# PiHatTeensy32_40.net
KiCad netlist of a schematic drawn in EAGLE
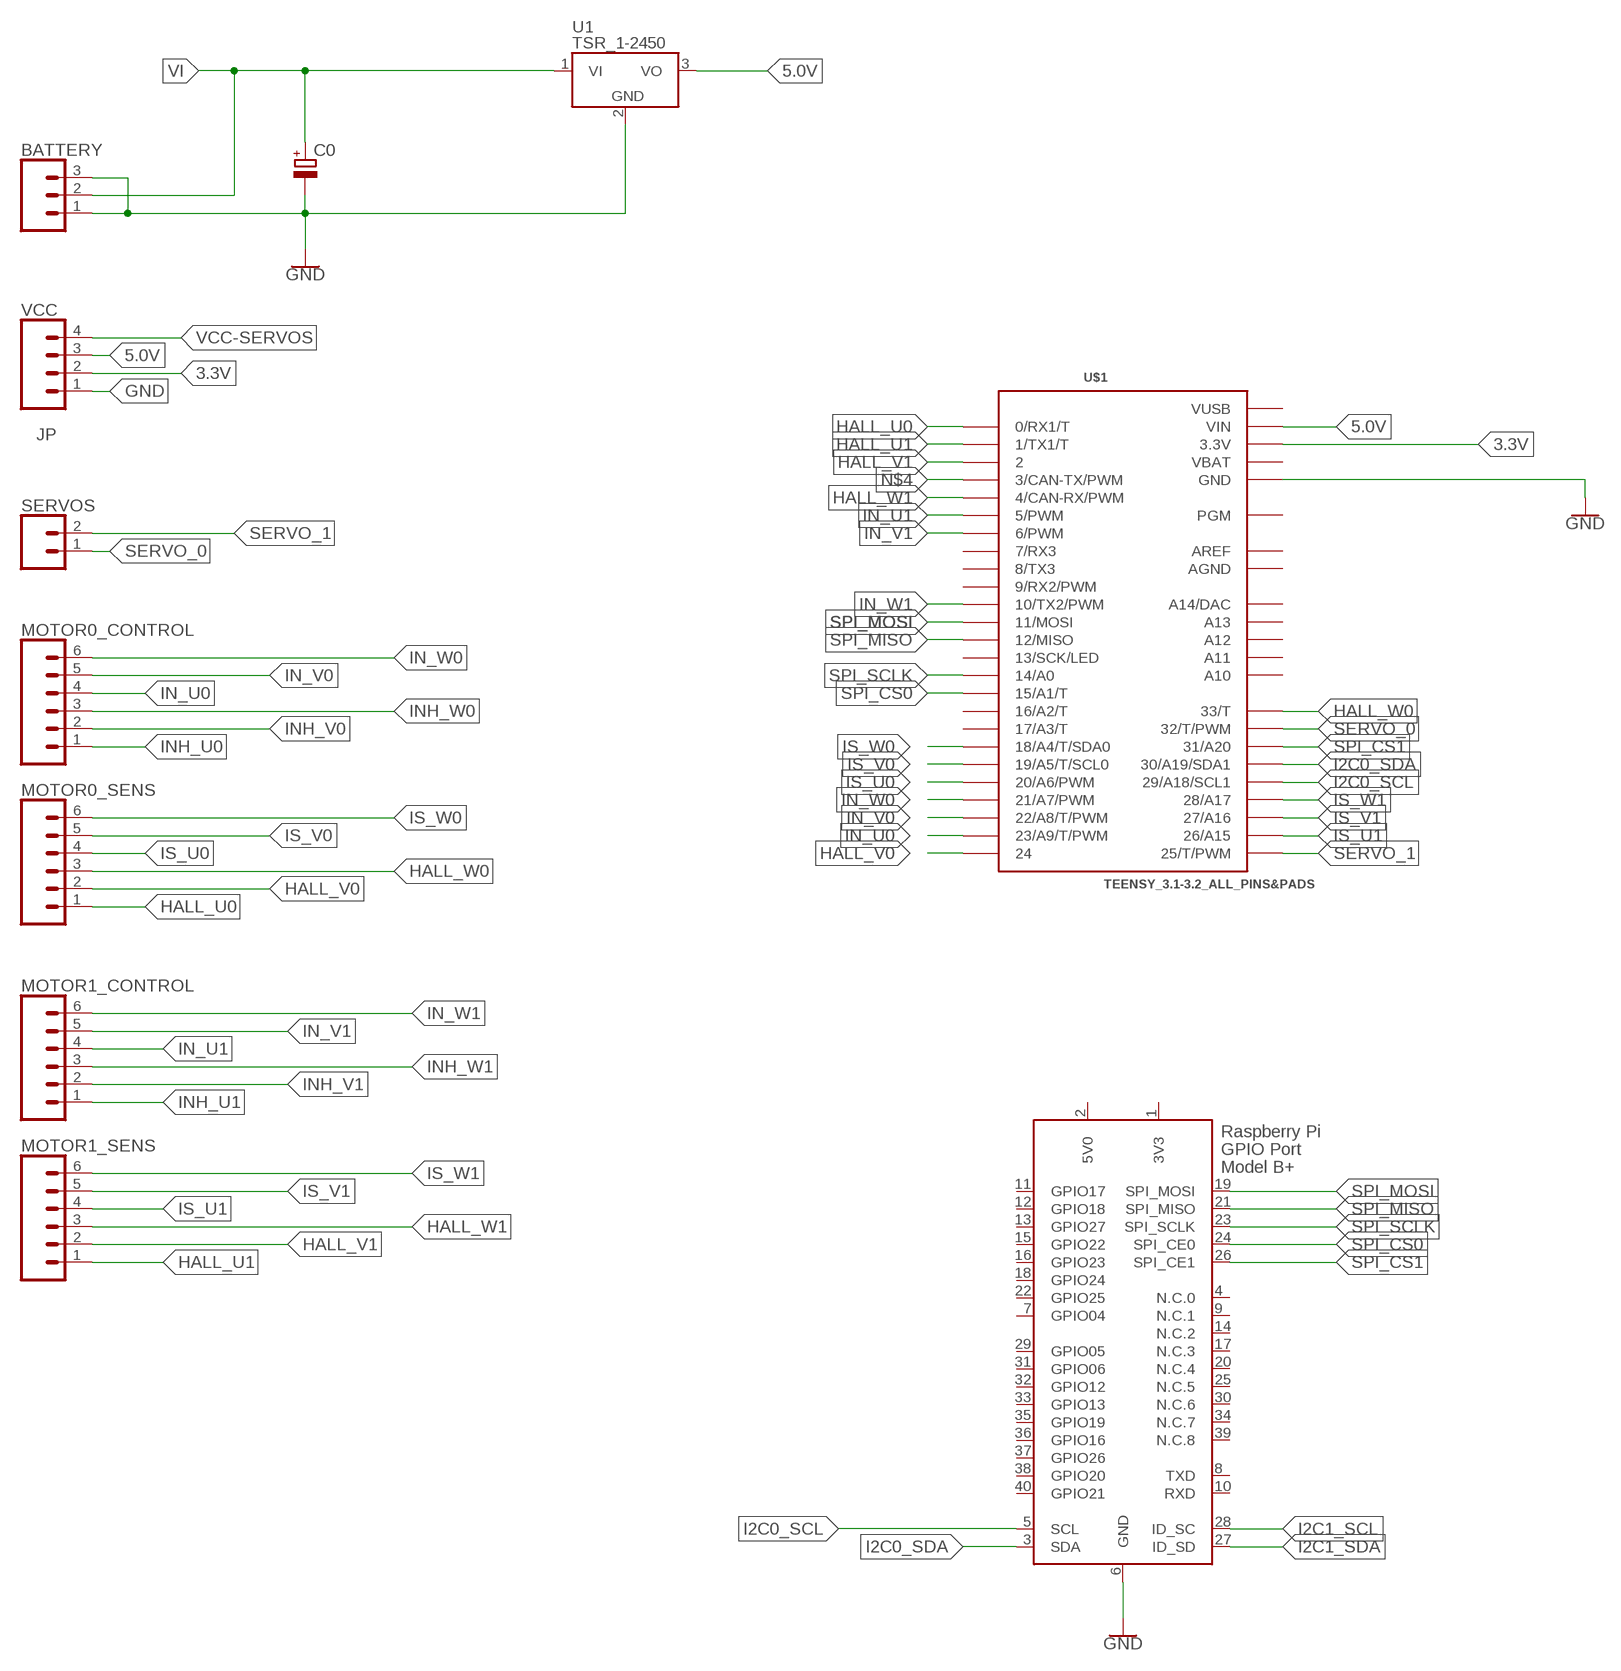
[diagram p0: schematic, sheet 1]

(export (version "E")
  (design (tool "Eeschema 10.0.6"))
  (components
    (comp (ref "BATTERY")
      (value "CONN_031X03_NO_SILK")
      (footprint "eagle-import:1X03_NO_SILK")
      (libsource (lib "eagle-import") (part "CONN_031X03_NO_SILK"))
    )
    (comp (ref "C0")
      (value "CPOL-EUE2,5-6E")
      (footprint "eagle-import:E2,5-6E")
      (libsource (lib "eagle-import") (part "CPOL-EUE2,5-6E"))
    )
    (comp (ref "MOTOR0_CONTROL")
      (value "CONN_06NO_SILK_NO_POP")
      (footprint "eagle-import:1X06_NO_SILK")
      (libsource (lib "eagle-import") (part "CONN_06NO_SILK_NO_POP"))
    )
    (comp (ref "MOTOR0_SENS")
      (value "CONN_06NO_SILK_NO_POP")
      (footprint "eagle-import:1X06_NO_SILK")
      (libsource (lib "eagle-import") (part "CONN_06NO_SILK_NO_POP"))
    )
    (comp (ref "MOTOR1_CONTROL")
      (value "CONN_06NO_SILK_NO_POP")
      (footprint "eagle-import:1X06_NO_SILK")
      (libsource (lib "eagle-import") (part "CONN_06NO_SILK_NO_POP"))
    )
    (comp (ref "MOTOR1_SENS")
      (value "CONN_06NO_SILK_NO_POP")
      (footprint "eagle-import:1X06_NO_SILK")
      (libsource (lib "eagle-import") (part "CONN_06NO_SILK_NO_POP"))
    )
    (comp (ref "SERVOS")
      (value "CONN_021X02_NO_SILK")
      (footprint "eagle-import:1X02_NO_SILK")
      (libsource (lib "eagle-import") (part "CONN_021X02_NO_SILK"))
    )
    (comp (ref "U$1")
      (value "TEENSY_3.1-3.2_ALL_PINS&PADS")
      (footprint "eagle-import:TEENSY_3.0-3.2_ALL_PINS_&_PADS")
      (libsource (lib "eagle-import") (part "TEENSY_3.1-3.2_ALL_PINS&PADS"))
    )
    (comp (ref "U1")
      (value "TSR_1-2450")
      (footprint "eagle-import:TSR-1")
      (libsource (lib "eagle-import") (part "TSR_1-2450"))
    )
    (comp (ref "VCC")
      (value "JP")
      (footprint "eagle-import:1X04_NO_SILK")
      (libsource (lib "eagle-import") (part "CONN_041X04_NO_SILK"))
    )
    (comp (ref "X1")
      (value "RASPI_BOARD_B+_H")
      (footprint "eagle-import:RASPI_BOARD_B+HAT")
      (libsource (lib "eagle-import") (part "RASPI_BOARD_B+_H"))
    )
  )
  (nets
    (net (code "1") (name "/3V3") (class "Default")
      (node (ref "X1") (pin "1") (pinfunction "3V3_1") (pintype "power_in"))
    )
    (net (code "2") (name "/5V0") (class "Default")
      (node (ref "X1") (pin "2") (pinfunction "5V0_2") (pintype "power_in"))
    )
    (net (code "3") (name "/AGND") (class "Default")
      (node (ref "U$1") (pin "AGND") (pinfunction "AGND_AGND") (pintype "power_in"))
    )
    (net (code "4") (name "/AREF") (class "Default")
      (node (ref "U$1") (pin "AREF") (pinfunction "AREF_AREF") (pintype "power_in"))
    )
    (net (code "5") (name "/VBAT") (class "Default")
      (node (ref "U$1") (pin "VBAT") (pinfunction "VBAT_VBAT") (pintype "power_in"))
    )
    (net (code "6") (name "/VUSB") (class "Default")
      (node (ref "U$1") (pin "VUSB") (pinfunction "VUSB_VUSB") (pintype "power_in"))
    )
    (net (code "7") (name "3.3V") (class "Default")
      (node (ref "U$1") (pin "3.3V") (pinfunction "3.3V_3.3V") (pintype "power_in"))
      (node (ref "U$1") (pin "3.3V1") (pinfunction "3.3V_3.3V1") (pintype "power_in"))
      (node (ref "U$1") (pin "3.3V2") (pinfunction "3.3V_3.3V2") (pintype "power_in"))
      (node (ref "VCC") (pin "2") (pinfunction "2_2") (pintype "passive"))
    )
    (net (code "8") (name "5.0V") (class "Default")
      (node (ref "U$1") (pin "VIN") (pinfunction "VIN_VIN") (pintype "power_in"))
      (node (ref "U1") (pin "3") (pinfunction "VO_3") (pintype "power_in"))
      (node (ref "VCC") (pin "3") (pinfunction "3_3") (pintype "passive"))
    )
    (net (code "9") (name "GND") (class "Default")
      (node (ref "BATTERY") (pin "1") (pinfunction "1_1") (pintype "passive"))
      (node (ref "BATTERY") (pin "3") (pinfunction "3_3") (pintype "passive"))
      (node (ref "C0") (pin "-") (pinfunction "-_-") (pintype "passive"))
      (node (ref "U$1") (pin "GND") (pinfunction "GND_GND") (pintype "power_in"))
      (node (ref "U$1") (pin "GND1") (pinfunction "GND_GND1") (pintype "power_in"))
      (node (ref "U$1") (pin "GND2") (pinfunction "GND_GND2") (pintype "power_in"))
      (node (ref "U1") (pin "2") (pinfunction "GND_2") (pintype "power_in"))
      (node (ref "VCC") (pin "1") (pinfunction "1_1") (pintype "passive"))
      (node (ref "X1") (pin "6") (pinfunction "GND_6") (pintype "power_in"))
    )
    (net (code "10") (name "HALL_U0") (class "Default")
      (node (ref "MOTOR0_SENS") (pin "1") (pinfunction "1_1") (pintype "passive"))
      (node (ref "U$1") (pin "0") (pinfunction "0/RX1/T_0") (pintype "bidirectional"))
    )
    (net (code "11") (name "HALL_U1") (class "Default")
      (node (ref "MOTOR1_SENS") (pin "1") (pinfunction "1_1") (pintype "passive"))
      (node (ref "U$1") (pin "1") (pinfunction "1/TX1/T_1") (pintype "bidirectional"))
    )
    (net (code "12") (name "HALL_V0") (class "Default")
      (node (ref "MOTOR0_SENS") (pin "2") (pinfunction "2_2") (pintype "passive"))
      (node (ref "U$1") (pin "24") (pinfunction "24_24") (pintype "bidirectional"))
    )
    (net (code "13") (name "HALL_V1") (class "Default")
      (node (ref "MOTOR1_SENS") (pin "2") (pinfunction "2_2") (pintype "passive"))
      (node (ref "U$1") (pin "2") (pinfunction "2_2") (pintype "bidirectional"))
    )
    (net (code "14") (name "HALL_W0") (class "Default")
      (node (ref "MOTOR0_SENS") (pin "3") (pinfunction "3_3") (pintype "passive"))
      (node (ref "U$1") (pin "33") (pinfunction "33/T_33") (pintype "bidirectional"))
    )
    (net (code "15") (name "HALL_W1") (class "Default")
      (node (ref "MOTOR1_SENS") (pin "3") (pinfunction "3_3") (pintype "passive"))
      (node (ref "U$1") (pin "4") (pinfunction "4/CAN-RX/PWM_4") (pintype "bidirectional"))
    )
    (net (code "16") (name "I2C0_SCL") (class "Default")
      (node (ref "U$1") (pin "29") (pinfunction "29/A18/SCL1_29") (pintype "bidirectional"))
      (node (ref "X1") (pin "5") (pinfunction "SCL_5") (pintype "bidirectional"))
    )
    (net (code "17") (name "I2C0_SDA") (class "Default")
      (node (ref "U$1") (pin "30") (pinfunction "30/A19/SDA1_30") (pintype "bidirectional"))
      (node (ref "X1") (pin "3") (pinfunction "SDA_3") (pintype "bidirectional"))
    )
    (net (code "20") (name "I2C1_SCL") (class "Default")
      (node (ref "X1") (pin "28") (pinfunction "ID_SC_28") (pintype "no_connect"))
    )
    (net (code "21") (name "I2C1_SDA") (class "Default")
      (node (ref "X1") (pin "27") (pinfunction "ID_SD_27") (pintype "no_connect"))
    )
    (net (code "22") (name "INH_U0") (class "Default")
      (node (ref "MOTOR0_CONTROL") (pin "1") (pinfunction "1_1") (pintype "passive"))
    )
    (net (code "23") (name "INH_U1") (class "Default")
      (node (ref "MOTOR1_CONTROL") (pin "1") (pinfunction "1_1") (pintype "passive"))
    )
    (net (code "24") (name "INH_V0") (class "Default")
      (node (ref "MOTOR0_CONTROL") (pin "2") (pinfunction "2_2") (pintype "passive"))
    )
    (net (code "25") (name "INH_V1") (class "Default")
      (node (ref "MOTOR1_CONTROL") (pin "2") (pinfunction "2_2") (pintype "passive"))
    )
    (net (code "26") (name "INH_W0") (class "Default")
      (node (ref "MOTOR0_CONTROL") (pin "3") (pinfunction "3_3") (pintype "passive"))
    )
    (net (code "27") (name "INH_W1") (class "Default")
      (node (ref "MOTOR1_CONTROL") (pin "3") (pinfunction "3_3") (pintype "passive"))
    )
    (net (code "28") (name "IN_U0") (class "Default")
      (node (ref "MOTOR0_CONTROL") (pin "4") (pinfunction "4_4") (pintype "passive"))
      (node (ref "U$1") (pin "23/A9") (pinfunction "23/A9/T/PWM_23/A9") (pintype "bidirectional"))
    )
    (net (code "29") (name "IN_U1") (class "Default")
      (node (ref "MOTOR1_CONTROL") (pin "4") (pinfunction "4_4") (pintype "passive"))
      (node (ref "U$1") (pin "5") (pinfunction "5/PWM_5") (pintype "bidirectional"))
    )
    (net (code "30") (name "IN_V0") (class "Default")
      (node (ref "MOTOR0_CONTROL") (pin "5") (pinfunction "5_5") (pintype "passive"))
      (node (ref "U$1") (pin "22/A8") (pinfunction "22/A8/T/PWM_22/A8") (pintype "bidirectional"))
    )
    (net (code "31") (name "IN_V1") (class "Default")
      (node (ref "MOTOR1_CONTROL") (pin "5") (pinfunction "5_5") (pintype "passive"))
      (node (ref "U$1") (pin "6") (pinfunction "6/PWM_6") (pintype "bidirectional"))
    )
    (net (code "32") (name "IN_W0") (class "Default")
      (node (ref "MOTOR0_CONTROL") (pin "6") (pinfunction "6_6") (pintype "passive"))
      (node (ref "U$1") (pin "21/A7") (pinfunction "21/A7/PWM_21/A7") (pintype "bidirectional"))
    )
    (net (code "33") (name "IN_W1") (class "Default")
      (node (ref "MOTOR1_CONTROL") (pin "6") (pinfunction "6_6") (pintype "passive"))
      (node (ref "U$1") (pin "10") (pinfunction "10/TX2/PWM_10") (pintype "bidirectional"))
    )
    (net (code "34") (name "IS_U0") (class "Default")
      (node (ref "MOTOR0_SENS") (pin "4") (pinfunction "4_4") (pintype "passive"))
      (node (ref "U$1") (pin "20/A6") (pinfunction "20/A6/PWM_20/A6") (pintype "bidirectional"))
    )
    (net (code "35") (name "IS_U1") (class "Default")
      (node (ref "MOTOR1_SENS") (pin "4") (pinfunction "4_4") (pintype "passive"))
      (node (ref "U$1") (pin "26") (pinfunction "26/A15_26") (pintype "bidirectional"))
    )
    (net (code "36") (name "IS_V0") (class "Default")
      (node (ref "MOTOR0_SENS") (pin "5") (pinfunction "5_5") (pintype "passive"))
      (node (ref "U$1") (pin "19/A5") (pinfunction "19/A5/T/SCL0_19/A5") (pintype "bidirectional"))
    )
    (net (code "37") (name "IS_V1") (class "Default")
      (node (ref "MOTOR1_SENS") (pin "5") (pinfunction "5_5") (pintype "passive"))
      (node (ref "U$1") (pin "27") (pinfunction "27/A16_27") (pintype "bidirectional"))
    )
    (net (code "38") (name "IS_W0") (class "Default")
      (node (ref "MOTOR0_SENS") (pin "6") (pinfunction "6_6") (pintype "passive"))
      (node (ref "U$1") (pin "18/A4") (pinfunction "18/A4/T/SDA0_18/A4") (pintype "bidirectional"))
    )
    (net (code "39") (name "IS_W1") (class "Default")
      (node (ref "MOTOR1_SENS") (pin "6") (pinfunction "6_6") (pintype "passive"))
      (node (ref "U$1") (pin "28") (pinfunction "28/A17_28") (pintype "bidirectional"))
    )
    (net (code "40") (name "N$4") (class "Default")
      (node (ref "U$1") (pin "3") (pinfunction "3/CAN-TX/PWM_3") (pintype "bidirectional"))
    )
    (net (code "41") (name "SERVO_0") (class "Default")
      (node (ref "SERVOS") (pin "1") (pinfunction "1_1") (pintype "passive"))
      (node (ref "U$1") (pin "32") (pinfunction "32/T/PWM_32") (pintype "bidirectional"))
    )
    (net (code "42") (name "SERVO_1") (class "Default")
      (node (ref "SERVOS") (pin "2") (pinfunction "2_2") (pintype "passive"))
      (node (ref "U$1") (pin "25") (pinfunction "25/T/PWM_25") (pintype "bidirectional"))
    )
    (net (code "43") (name "SPI_CS0") (class "Default")
      (node (ref "U$1") (pin "15/A1") (pinfunction "15/A1/T_15/A1") (pintype "bidirectional"))
      (node (ref "X1") (pin "24") (pinfunction "SPI_CE0_24") (pintype "bidirectional"))
    )
    (net (code "44") (name "SPI_CS1") (class "Default")
      (node (ref "U$1") (pin "31") (pinfunction "31/A20_31") (pintype "bidirectional"))
      (node (ref "X1") (pin "26") (pinfunction "SPI_CE1_26") (pintype "bidirectional"))
    )
    (net (code "45") (name "SPI_MISO") (class "Default")
      (node (ref "U$1") (pin "12") (pinfunction "12/MISO_12") (pintype "bidirectional"))
      (node (ref "X1") (pin "21") (pinfunction "SPI_MISO_21") (pintype "bidirectional"))
    )
    (net (code "46") (name "SPI_MOSI") (class "Default")
      (node (ref "U$1") (pin "11") (pinfunction "11/MOSI_11") (pintype "bidirectional"))
      (node (ref "X1") (pin "19") (pinfunction "SPI_MOSI_19") (pintype "bidirectional"))
    )
    (net (code "47") (name "SPI_SCLK") (class "Default")
      (node (ref "U$1") (pin "14/A0") (pinfunction "14/A0_14/A0") (pintype "bidirectional"))
      (node (ref "X1") (pin "23") (pinfunction "SPI_SCLK_23") (pintype "bidirectional"))
    )
    (net (code "48") (name "VCC-SERVOS") (class "Default")
      (node (ref "VCC") (pin "4") (pinfunction "4_4") (pintype "passive"))
    )
    (net (code "49") (name "VI") (class "Default")
      (node (ref "BATTERY") (pin "2") (pinfunction "2_2") (pintype "passive"))
      (node (ref "C0") (pin "+") (pinfunction "+_+") (pintype "passive"))
      (node (ref "U1") (pin "1") (pinfunction "VI_1") (pintype "power_in"))
    )
    (net (code "50") (name "unconnected-(U$1-7{slash}RX3-Pad7)") (class "Default")
      (node (ref "U$1") (pin "7") (pinfunction "7/RX3_7") (pintype "bidirectional"))
    )
    (net (code "51") (name "unconnected-(U$1-8{slash}TX3-Pad8)") (class "Default")
      (node (ref "U$1") (pin "8") (pinfunction "8/TX3_8") (pintype "bidirectional"))
    )
    (net (code "52") (name "unconnected-(U$1-9{slash}RX2{slash}PWM-Pad9)") (class "Default")
      (node (ref "U$1") (pin "9") (pinfunction "9/RX2/PWM_9") (pintype "bidirectional"))
    )
    (net (code "53") (name "unconnected-(U$1-13{slash}SCK{slash}LED-Pad13)") (class "Default")
      (node (ref "U$1") (pin "13") (pinfunction "13/SCK/LED_13") (pintype "bidirectional"))
    )
    (net (code "54") (name "unconnected-(U$1-16{slash}A2{slash}T-Pad16{slash}A2)") (class "Default")
      (node (ref "U$1") (pin "16/A2") (pinfunction "16/A2/T_16/A2") (pintype "bidirectional"))
    )
    (net (code "55") (name "unconnected-(U$1-17{slash}A3{slash}T-Pad17{slash}A3)") (class "Default")
      (node (ref "U$1") (pin "17/A3") (pinfunction "17/A3/T_17/A3") (pintype "bidirectional"))
    )
    (net (code "56") (name "unconnected-(U$1-A14{slash}DAC-PadRESET{slash}DAC)") (class "Default")
      (node (ref "U$1") (pin "RESET/DAC") (pinfunction "A14/DAC_RESET/DAC") (pintype "bidirectional"))
    )
    (net (code "57") (name "unconnected-(U$1-PadA10)") (class "Default")
      (node (ref "U$1") (pin "A10") (pinfunction "A10_A10") (pintype "bidirectional"))
    )
    (net (code "58") (name "unconnected-(U$1-PadA11)") (class "Default")
      (node (ref "U$1") (pin "A11") (pinfunction "A11_A11") (pintype "bidirectional"))
    )
    (net (code "59") (name "unconnected-(U$1-PadA12)") (class "Default")
      (node (ref "U$1") (pin "A12") (pinfunction "A12_A12") (pintype "bidirectional"))
    )
    (net (code "60") (name "unconnected-(U$1-PadA13)") (class "Default")
      (node (ref "U$1") (pin "A13") (pinfunction "A13_A13") (pintype "bidirectional"))
    )
    (net (code "61") (name "unconnected-(U$1-PadPGM)") (class "Default")
      (node (ref "U$1") (pin "PGM") (pinfunction "PGM_PGM") (pintype "bidirectional"))
    )
    (net (code "62") (name "unconnected-(X1-GPIO04-Pad7)") (class "Default")
      (node (ref "X1") (pin "7") (pinfunction "GPIO04_7") (pintype "bidirectional"))
    )
    (net (code "63") (name "unconnected-(X1-GPIO05-Pad29)") (class "Default")
      (node (ref "X1") (pin "29") (pinfunction "GPIO05_29") (pintype "no_connect"))
    )
    (net (code "64") (name "unconnected-(X1-GPIO06-Pad31)") (class "Default")
      (node (ref "X1") (pin "31") (pinfunction "GPIO06_31") (pintype "no_connect"))
    )
    (net (code "65") (name "unconnected-(X1-GPIO12-Pad32)") (class "Default")
      (node (ref "X1") (pin "32") (pinfunction "GPIO12_32") (pintype "no_connect"))
    )
    (net (code "66") (name "unconnected-(X1-GPIO13-Pad33)") (class "Default")
      (node (ref "X1") (pin "33") (pinfunction "GPIO13_33") (pintype "no_connect"))
    )
    (net (code "67") (name "unconnected-(X1-GPIO16-Pad36)") (class "Default")
      (node (ref "X1") (pin "36") (pinfunction "GPIO16_36") (pintype "no_connect"))
    )
    (net (code "68") (name "unconnected-(X1-GPIO17-Pad11)") (class "Default")
      (node (ref "X1") (pin "11") (pinfunction "GPIO17_11") (pintype "bidirectional"))
    )
    (net (code "69") (name "unconnected-(X1-GPIO18-Pad12)") (class "Default")
      (node (ref "X1") (pin "12") (pinfunction "GPIO18_12") (pintype "bidirectional"))
    )
    (net (code "70") (name "unconnected-(X1-GPIO19-Pad35)") (class "Default")
      (node (ref "X1") (pin "35") (pinfunction "GPIO19_35") (pintype "no_connect"))
    )
    (net (code "71") (name "unconnected-(X1-GPIO20-Pad38)") (class "Default")
      (node (ref "X1") (pin "38") (pinfunction "GPIO20_38") (pintype "no_connect"))
    )
    (net (code "72") (name "unconnected-(X1-GPIO21-Pad40)") (class "Default")
      (node (ref "X1") (pin "40") (pinfunction "GPIO21_40") (pintype "no_connect"))
    )
    (net (code "73") (name "unconnected-(X1-GPIO22-Pad15)") (class "Default")
      (node (ref "X1") (pin "15") (pinfunction "GPIO22_15") (pintype "bidirectional"))
    )
    (net (code "74") (name "unconnected-(X1-GPIO23-Pad16)") (class "Default")
      (node (ref "X1") (pin "16") (pinfunction "GPIO23_16") (pintype "bidirectional"))
    )
    (net (code "75") (name "unconnected-(X1-GPIO24-Pad18)") (class "Default")
      (node (ref "X1") (pin "18") (pinfunction "GPIO24_18") (pintype "bidirectional"))
    )
    (net (code "76") (name "unconnected-(X1-GPIO25-Pad22)") (class "Default")
      (node (ref "X1") (pin "22") (pinfunction "GPIO25_22") (pintype "bidirectional"))
    )
    (net (code "77") (name "unconnected-(X1-GPIO26-Pad37)") (class "Default")
      (node (ref "X1") (pin "37") (pinfunction "GPIO26_37") (pintype "no_connect"))
    )
    (net (code "78") (name "unconnected-(X1-GPIO27-Pad13)") (class "Default")
      (node (ref "X1") (pin "13") (pinfunction "GPIO27_13") (pintype "bidirectional"))
    )
    (net (code "79") (name "unconnected-(X1-N.C.0-Pad4)") (class "Default")
      (node (ref "X1") (pin "4") (pinfunction "N.C.0_4") (pintype "no_connect"))
    )
    (net (code "80") (name "unconnected-(X1-N.C.1-Pad9)") (class "Default")
      (node (ref "X1") (pin "9") (pinfunction "N.C.1_9") (pintype "no_connect"))
    )
    (net (code "81") (name "unconnected-(X1-N.C.2-Pad14)") (class "Default")
      (node (ref "X1") (pin "14") (pinfunction "N.C.2_14") (pintype "no_connect"))
    )
    (net (code "82") (name "unconnected-(X1-N.C.3-Pad17)") (class "Default")
      (node (ref "X1") (pin "17") (pinfunction "N.C.3_17") (pintype "no_connect"))
    )
    (net (code "83") (name "unconnected-(X1-N.C.4-Pad20)") (class "Default")
      (node (ref "X1") (pin "20") (pinfunction "N.C.4_20") (pintype "no_connect"))
    )
    (net (code "84") (name "unconnected-(X1-N.C.5-Pad25)") (class "Default")
      (node (ref "X1") (pin "25") (pinfunction "N.C.5_25") (pintype "no_connect"))
    )
    (net (code "85") (name "unconnected-(X1-N.C.6-Pad30)") (class "Default")
      (node (ref "X1") (pin "30") (pinfunction "N.C.6_30") (pintype "no_connect"))
    )
    (net (code "86") (name "unconnected-(X1-N.C.7-Pad34)") (class "Default")
      (node (ref "X1") (pin "34") (pinfunction "N.C.7_34") (pintype "no_connect"))
    )
    (net (code "87") (name "unconnected-(X1-N.C.8-Pad39)") (class "Default")
      (node (ref "X1") (pin "39") (pinfunction "N.C.8_39") (pintype "no_connect"))
    )
    (net (code "88") (name "unconnected-(X1-RXD-Pad10)") (class "Default")
      (node (ref "X1") (pin "10") (pinfunction "RXD_10") (pintype "bidirectional"))
    )
    (net (code "89") (name "unconnected-(X1-TXD-Pad8)") (class "Default")
      (node (ref "X1") (pin "8") (pinfunction "TXD_8") (pintype "bidirectional"))
    )
  )
)
